# ardustatversion9.net
KiCad netlist of a schematic drawn in EAGLE
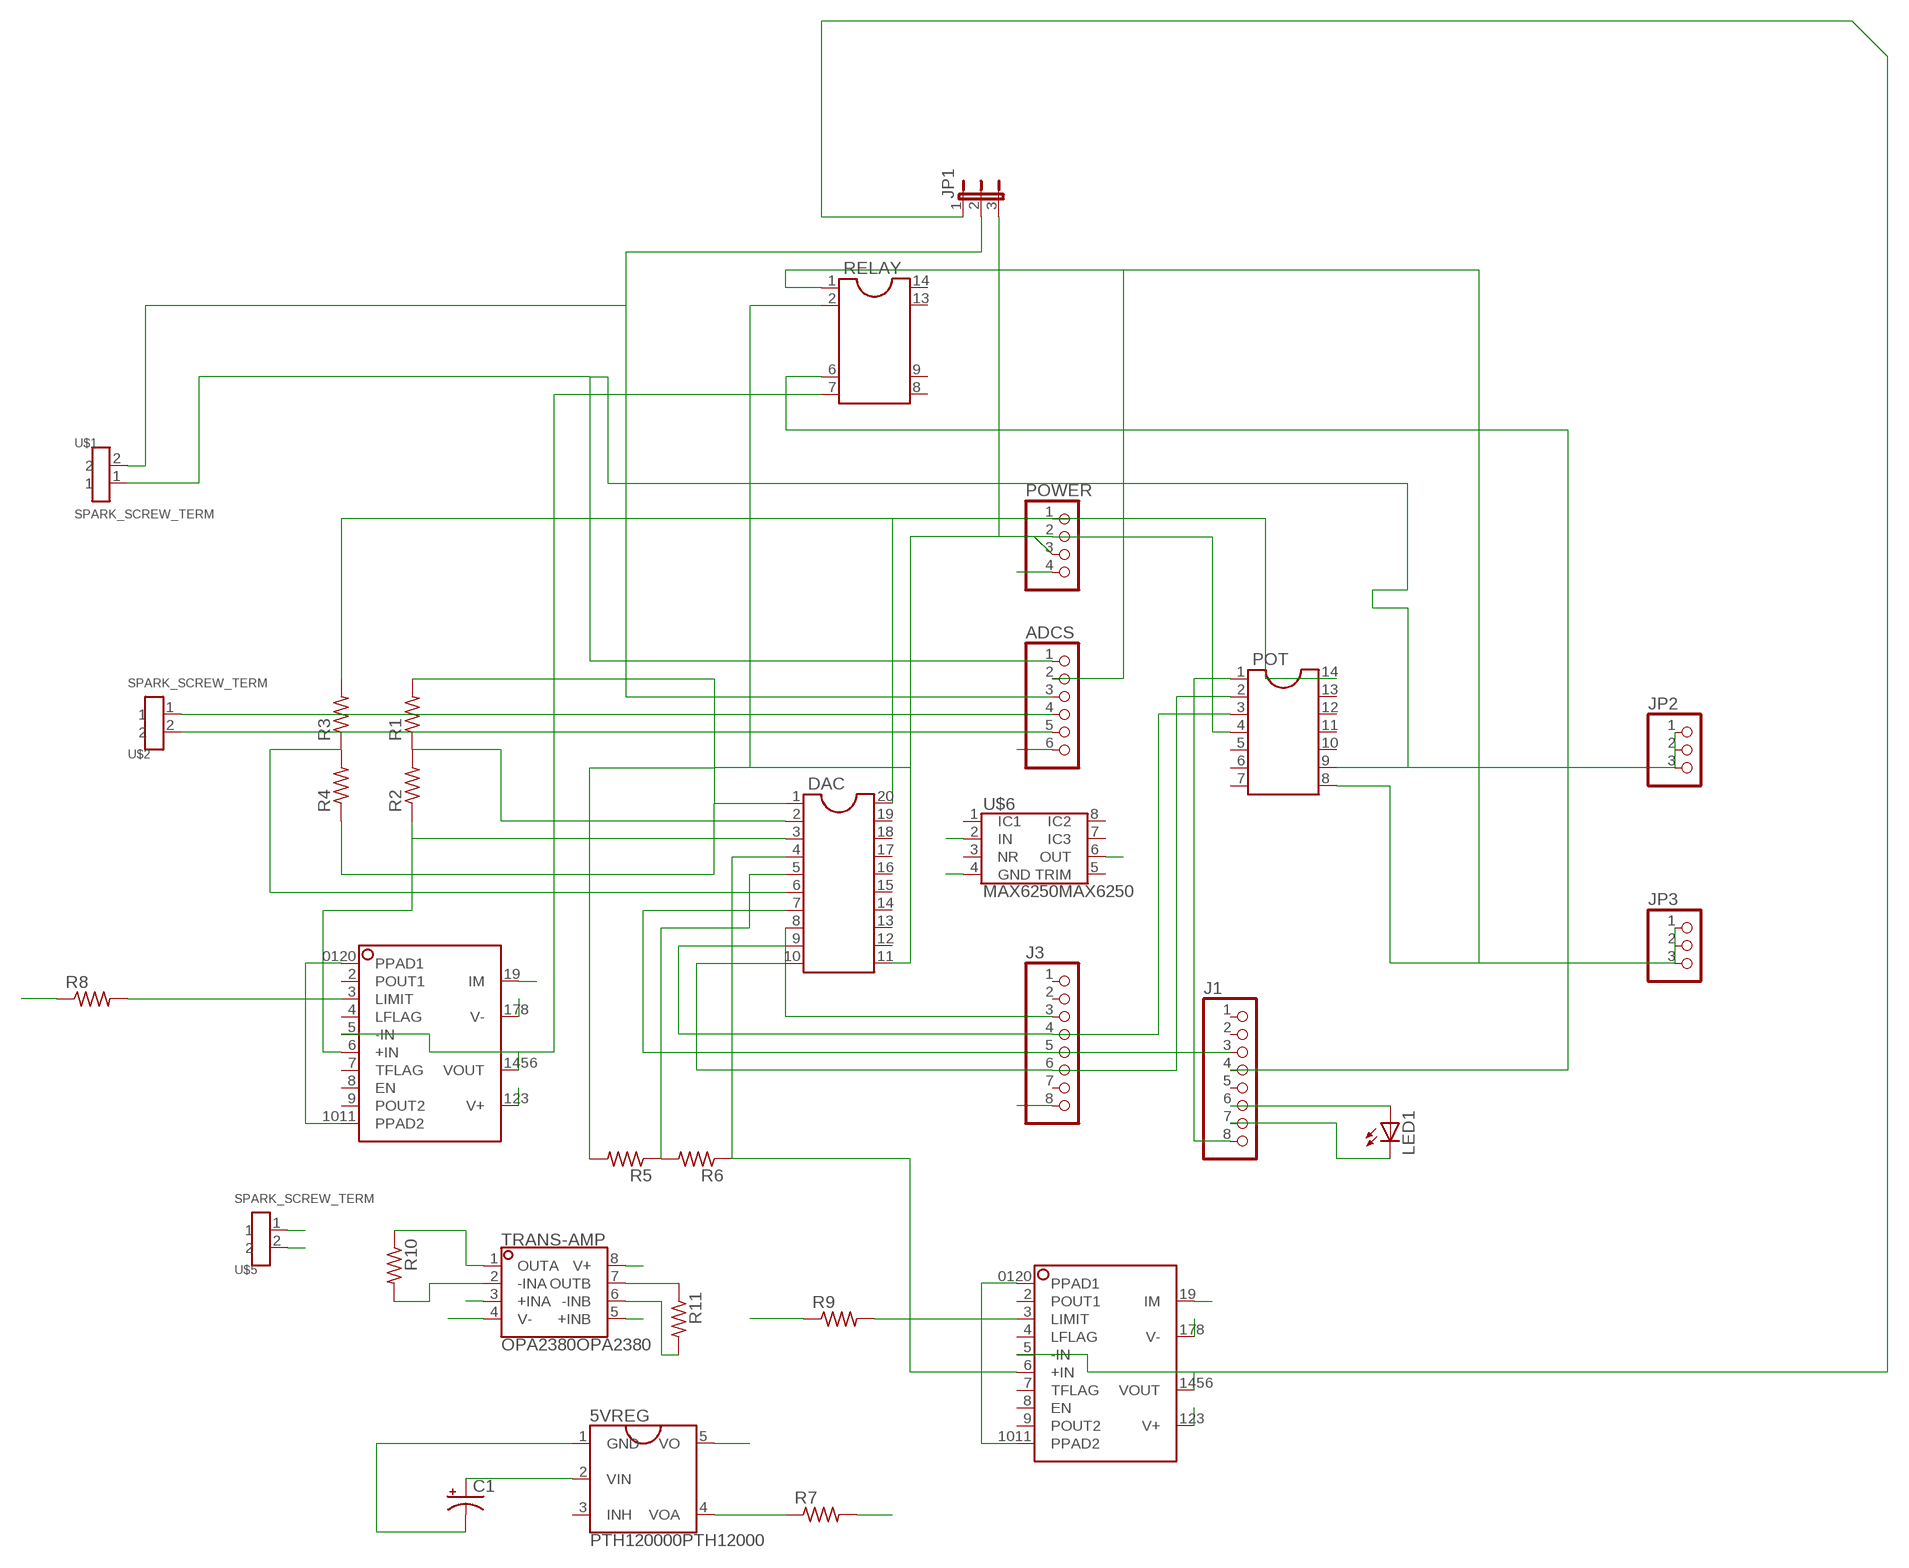
[diagram p0: schematic, sheet 1]

(export (version "E")
  (design (tool "Eeschema 10.0.6"))
  (components
    (comp (ref "5VREG")
      (value "PTH120000PTH12000")
      (footprint "eagle-import:PTH120000")
      (libsource (lib "eagle-import") (part "PTH120000PTH12000"))
    )
    (comp (ref "ADCS")
      (value "PINHD-1X6")
      (footprint "eagle-import:1X06")
      (libsource (lib "eagle-import") (part "PINHD-1X6"))
    )
    (comp (ref "C1")
      (value "CPOL-USE5-10.5")
      (footprint "eagle-import:E5-10,5")
      (libsource (lib "eagle-import") (part "CPOL-USE5-10.5"))
    )
    (comp (ref "DAC")
      (value "DIL20S")
      (footprint "eagle-import:SOCKED-20")
      (libsource (lib "eagle-import") (part "DIL20S"))
    )
    (comp (ref "J1")
      (value "PINHD-1X8")
      (footprint "eagle-import:1X08")
      (libsource (lib "eagle-import") (part "PINHD-1X8"))
    )
    (comp (ref "J3")
      (value "PINHD-1X8")
      (footprint "eagle-import:1X08")
      (libsource (lib "eagle-import") (part "PINHD-1X8"))
    )
    (comp (ref "JP1")
      (value "JP2E")
      (footprint "eagle-import:JP2")
      (libsource (lib "eagle-import") (part "JP2E"))
    )
    (comp (ref "JP2")
      (value "PINHD-1X3")
      (footprint "eagle-import:1X03")
      (libsource (lib "eagle-import") (part "PINHD-1X3"))
    )
    (comp (ref "JP3")
      (value "PINHD-1X3")
      (footprint "eagle-import:1X03")
      (libsource (lib "eagle-import") (part "PINHD-1X3"))
    )
    (comp (ref "LED1")
      (value "LED5MM")
      (footprint "eagle-import:LED5MM")
      (libsource (lib "eagle-import") (part "LED5MM"))
    )
    (comp (ref "POT")
      (value "DIL14S")
      (footprint "eagle-import:SOCKET-14")
      (libsource (lib "eagle-import") (part "DIL14S"))
    )
    (comp (ref "POWER")
      (value "PINHD-1X4")
      (footprint "eagle-import:1X04")
      (libsource (lib "eagle-import") (part "PINHD-1X4"))
    )
    (comp (ref "R1")
      (value "R-US_R1206")
      (footprint "eagle-import:R1206")
      (libsource (lib "eagle-import") (part "R-US_R1206"))
    )
    (comp (ref "R2")
      (value "R-US_R1206")
      (footprint "eagle-import:R1206")
      (libsource (lib "eagle-import") (part "resistor_R-US_R1206"))
    )
    (comp (ref "R3")
      (value "R-US_R1206")
      (footprint "eagle-import:R1206")
      (libsource (lib "eagle-import") (part "R-US_R1206"))
    )
    (comp (ref "R4")
      (value "R-US_R1206")
      (footprint "eagle-import:R1206")
      (libsource (lib "eagle-import") (part "R-US_R1206"))
    )
    (comp (ref "R5")
      (value "R-US_R1206")
      (footprint "eagle-import:R1206")
      (libsource (lib "eagle-import") (part "R-US_R1206"))
    )
    (comp (ref "R6")
      (value "R-US_R1206")
      (footprint "eagle-import:R1206")
      (libsource (lib "eagle-import") (part "R-US_R1206"))
    )
    (comp (ref "R7")
      (value "R-US_M1206")
      (footprint "eagle-import:M1206")
      (libsource (lib "eagle-import") (part "R-US_M1206"))
    )
    (comp (ref "R8")
      (value "R-US_R1206")
      (footprint "eagle-import:R1206")
      (libsource (lib "eagle-import") (part "R-US_R1206"))
    )
    (comp (ref "R9")
      (value "R-US_M1206")
      (footprint "eagle-import:M1206")
      (libsource (lib "eagle-import") (part "R-US_M1206"))
    )
    (comp (ref "R10")
      (value "R-US_M1206")
      (footprint "eagle-import:M1206")
      (libsource (lib "eagle-import") (part "R-US_M1206"))
    )
    (comp (ref "R11")
      (value "R-US_M1206")
      (footprint "eagle-import:M1206")
      (libsource (lib "eagle-import") (part "R-US_M1206"))
    )
    (comp (ref "RELAY")
      (value "DIL14/8")
      (footprint "eagle-import:DIL14_8")
      (libsource (lib "eagle-import") (part "DIL14/8"))
    )
    (comp (ref "TRANS-AMP")
      (value "OPA2380OPA2380")
      (footprint "eagle-import:OPA2380")
      (libsource (lib "eagle-import") (part "OPA2380OPA2380"))
    )
    (comp (ref "U$1")
      (value "SPARK_SCREW_TERM")
      (footprint "eagle-import:SPARK_SCREW_TERM")
      (libsource (lib "eagle-import") (part "SPARK_SCREW_TERM"))
    )
    (comp (ref "U$2")
      (value "SPARK_SCREW_TERM")
      (footprint "eagle-import:SPARK_SCREW_TERM")
      (libsource (lib "eagle-import") (part "SPARK_SCREW_TERM"))
    )
    (comp (ref "U$3")
      (value "OPA569OPA569")
      (footprint "eagle-import:OPA569")
      (libsource (lib "eagle-import") (part "OPA569OPA569"))
    )
    (comp (ref "U$4")
      (value "OPA569OPA569")
      (footprint "eagle-import:OPA569")
      (libsource (lib "eagle-import") (part "OPA569OPA569"))
    )
    (comp (ref "U$5")
      (value "SPARK_SCREW_TERM")
      (footprint "eagle-import:SPARK_SCREW_TERM")
      (libsource (lib "eagle-import") (part "SPARK_SCREW_TERM"))
    )
    (comp (ref "U$6")
      (value "MAX6250MAX6250")
      (footprint "eagle-import:MAX6250")
      (libsource (lib "eagle-import") (part "MAX6250MAX6250"))
    )
  )
  (nets
    (net (code "1") (name "/GND") (class "Default")
      (node (ref "5VREG") (pin "1") (pinfunction "GND_1") (pintype "power_in"))
      (node (ref "C1") (pin "-") (pinfunction "-_-") (pintype "passive"))
      (node (ref "DAC") (pin "1") (pinfunction "1_1") (pintype "passive"))
      (node (ref "DAC") (pin "11") (pinfunction "11_11") (pintype "passive"))
      (node (ref "JP1") (pin "3") (pinfunction "3_3") (pintype "passive"))
      (node (ref "POT") (pin "4") (pinfunction "4_4") (pintype "passive"))
      (node (ref "POWER") (pin "2") (pinfunction "2_2") (pintype "passive"))
      (node (ref "POWER") (pin "3") (pinfunction "3_3") (pintype "passive"))
      (node (ref "R1") (pin "2") (pinfunction "2_2") (pintype "passive"))
      (node (ref "R4") (pin "1") (pinfunction "1_1") (pintype "passive"))
      (node (ref "R5") (pin "2") (pinfunction "2_2") (pintype "passive"))
      (node (ref "R7") (pin "2") (pinfunction "2_2") (pintype "passive"))
      (node (ref "R8") (pin "1") (pinfunction "1_1") (pintype "passive"))
      (node (ref "R9") (pin "1") (pinfunction "1_1") (pintype "passive"))
      (node (ref "RELAY") (pin "2") (pinfunction "2_2") (pintype "passive"))
      (node (ref "TRANS-AMP") (pin "4") (pinfunction "V-_4") (pintype "power_in"))
      (node (ref "U$3") (pin "0120") (pinfunction "PPAD1_0120") (pintype "bidirectional"))
      (node (ref "U$3") (pin "1011") (pinfunction "PPAD2_1011") (pintype "bidirectional"))
      (node (ref "U$3") (pin "178") (pinfunction "V-_178") (pintype "bidirectional"))
      (node (ref "U$4") (pin "0120") (pinfunction "PPAD1_0120") (pintype "bidirectional"))
      (node (ref "U$4") (pin "1011") (pinfunction "PPAD2_1011") (pintype "bidirectional"))
      (node (ref "U$4") (pin "178") (pinfunction "V-_178") (pintype "bidirectional"))
      (node (ref "U$5") (pin "2") (pinfunction "2_2") (pintype "bidirectional"))
      (node (ref "U$6") (pin "4") (pinfunction "GND_4") (pintype "bidirectional"))
    )
    (net (code "2") (name "/N$10") (class "Default")
      (node (ref "R10") (pin "2") (pinfunction "2_2") (pintype "passive"))
      (node (ref "TRANS-AMP") (pin "2") (pinfunction "-INA_2") (pintype "input"))
      (node (ref "U$3") (pin "19") (pinfunction "IM_19") (pintype "bidirectional"))
    )
    (net (code "3") (name "/N$11") (class "Default")
      (node (ref "ADCS") (pin "2") (pinfunction "2_2") (pintype "passive"))
      (node (ref "JP3") (pin "1") (pinfunction "1_1") (pintype "passive"))
      (node (ref "JP3") (pin "2") (pinfunction "2_2") (pintype "passive"))
      (node (ref "JP3") (pin "3") (pinfunction "3_3") (pintype "passive"))
      (node (ref "POT") (pin "8") (pinfunction "8_8") (pintype "passive"))
      (node (ref "RELAY") (pin "1") (pinfunction "1_1") (pintype "passive"))
      (node (ref "TRANS-AMP") (pin "5") (pinfunction "+INB_5") (pintype "input"))
    )
    (net (code "4") (name "/N$14") (class "Default")
      (node (ref "ADCS") (pin "5") (pinfunction "5_5") (pintype "passive"))
      (node (ref "R10") (pin "1") (pinfunction "1_1") (pintype "passive"))
      (node (ref "TRANS-AMP") (pin "1") (pinfunction "OUTA_1") (pintype "output"))
      (node (ref "U$2") (pin "2") (pinfunction "2_2") (pintype "bidirectional"))
    )
    (net (code "5") (name "/N$19") (class "Default")
      (node (ref "5VREG") (pin "5") (pinfunction "VO_5") (pintype "bidirectional"))
      (node (ref "TRANS-AMP") (pin "8") (pinfunction "V+_8") (pintype "power_in"))
      (node (ref "U$3") (pin "123") (pinfunction "V+_123") (pintype "bidirectional"))
      (node (ref "U$4") (pin "123") (pinfunction "V+_123") (pintype "bidirectional"))
    )
    (net (code "6") (name "/N$21") (class "Default")
      (node (ref "ADCS") (pin "3") (pinfunction "3_3") (pintype "passive"))
      (node (ref "JP1") (pin "2") (pinfunction "2_2") (pintype "passive"))
      (node (ref "TRANS-AMP") (pin "3") (pinfunction "+INA_3") (pintype "input"))
      (node (ref "U$1") (pin "2") (pinfunction "2_2") (pintype "bidirectional"))
    )
    (net (code "7") (name "/N$22") (class "Default")
      (node (ref "5VREG") (pin "2") (pinfunction "VIN_2") (pintype "power_in"))
      (node (ref "C1") (pin "+") (pinfunction "+_+") (pintype "passive"))
      (node (ref "POWER") (pin "4") (pinfunction "4_4") (pintype "passive"))
      (node (ref "U$5") (pin "1") (pinfunction "1_1") (pintype "bidirectional"))
      (node (ref "U$6") (pin "2") (pinfunction "IN_2") (pintype "bidirectional"))
    )
    (net (code "8") (name "/N$24") (class "Default")
      (node (ref "J3") (pin "8") (pinfunction "8_8") (pintype "passive"))
      (node (ref "U$6") (pin "6") (pinfunction "OUT_6") (pintype "bidirectional"))
    )
    (net (code "9") (name "/N$48") (class "Default")
      (node (ref "ADCS") (pin "6") (pinfunction "6_6") (pintype "passive"))
      (node (ref "R11") (pin "1") (pinfunction "1_1") (pintype "passive"))
      (node (ref "TRANS-AMP") (pin "7") (pinfunction "OUTB_7") (pintype "output"))
    )
    (net (code "10") (name "/N$49") (class "Default")
      (node (ref "R11") (pin "2") (pinfunction "2_2") (pintype "passive"))
      (node (ref "TRANS-AMP") (pin "6") (pinfunction "-INB_6") (pintype "input"))
      (node (ref "U$4") (pin "19") (pinfunction "IM_19") (pintype "bidirectional"))
    )
    (net (code "11") (name "Net-(5VREG-VOA)") (class "Default")
      (node (ref "5VREG") (pin "4") (pinfunction "VOA_4") (pintype "input"))
      (node (ref "R7") (pin "1") (pinfunction "1_1") (pintype "passive"))
    )
    (net (code "12") (name "Net-(ADCS-Pad1)") (class "Default")
      (node (ref "ADCS") (pin "1") (pinfunction "1_1") (pintype "passive"))
      (node (ref "JP2") (pin "1") (pinfunction "1_1") (pintype "passive"))
      (node (ref "JP2") (pin "2") (pinfunction "2_2") (pintype "passive"))
      (node (ref "JP2") (pin "3") (pinfunction "3_3") (pintype "passive"))
      (node (ref "POT") (pin "9") (pinfunction "9_9") (pintype "passive"))
      (node (ref "U$1") (pin "1") (pinfunction "1_1") (pintype "bidirectional"))
    )
    (net (code "13") (name "Net-(ADCS-Pad4)") (class "Default")
      (node (ref "ADCS") (pin "4") (pinfunction "4_4") (pintype "passive"))
      (node (ref "U$2") (pin "1") (pinfunction "1_1") (pintype "bidirectional"))
    )
    (net (code "14") (name "Net-(DAC-Pad2)") (class "Default")
      (node (ref "DAC") (pin "2") (pinfunction "2_2") (pintype "passive"))
      (node (ref "R1") (pin "1") (pinfunction "1_1") (pintype "passive"))
      (node (ref "R2") (pin "2") (pinfunction "2_2") (pintype "passive"))
    )
    (net (code "15") (name "Net-(DAC-Pad5)") (class "Default")
      (node (ref "DAC") (pin "5") (pinfunction "5_5") (pintype "passive"))
      (node (ref "R5") (pin "1") (pinfunction "1_1") (pintype "passive"))
      (node (ref "R6") (pin "2") (pinfunction "2_2") (pintype "passive"))
    )
    (net (code "16") (name "Net-(DAC-Pad6)") (class "Default")
      (node (ref "DAC") (pin "6") (pinfunction "6_6") (pintype "passive"))
      (node (ref "R3") (pin "1") (pinfunction "1_1") (pintype "passive"))
      (node (ref "R4") (pin "2") (pinfunction "2_2") (pintype "passive"))
    )
    (net (code "17") (name "Net-(DAC-Pad7)") (class "Default")
      (node (ref "DAC") (pin "7") (pinfunction "7_7") (pintype "passive"))
      (node (ref "J1") (pin "3") (pinfunction "3_3") (pintype "passive"))
    )
    (net (code "18") (name "Net-(DAC-Pad8)") (class "Default")
      (node (ref "DAC") (pin "8") (pinfunction "8_8") (pintype "passive"))
      (node (ref "J3") (pin "3") (pinfunction "3_3") (pintype "passive"))
    )
    (net (code "19") (name "Net-(DAC-Pad9)") (class "Default")
      (node (ref "DAC") (pin "9") (pinfunction "9_9") (pintype "passive"))
      (node (ref "J3") (pin "4") (pinfunction "4_4") (pintype "passive"))
      (node (ref "POT") (pin "3") (pinfunction "3_3") (pintype "passive"))
    )
    (net (code "20") (name "Net-(DAC-Pad10)") (class "Default")
      (node (ref "DAC") (pin "10") (pinfunction "10_10") (pintype "passive"))
      (node (ref "J3") (pin "6") (pinfunction "6_6") (pintype "passive"))
      (node (ref "POT") (pin "2") (pinfunction "2_2") (pintype "passive"))
    )
    (net (code "21") (name "Net-(DAC-Pad20)") (class "Default")
      (node (ref "DAC") (pin "20") (pinfunction "20_20") (pintype "passive"))
      (node (ref "POT") (pin "14") (pinfunction "14_14") (pintype "passive"))
      (node (ref "POWER") (pin "1") (pinfunction "1_1") (pintype "passive"))
      (node (ref "R3") (pin "2") (pinfunction "2_2") (pintype "passive"))
    )
    (net (code "22") (name "Net-(J1-Pad4)") (class "Default")
      (node (ref "J1") (pin "4") (pinfunction "4_4") (pintype "passive"))
      (node (ref "RELAY") (pin "6") (pinfunction "6_6") (pintype "passive"))
    )
    (net (code "23") (name "Net-(J1-Pad6)") (class "Default")
      (node (ref "J1") (pin "6") (pinfunction "6_6") (pintype "passive"))
      (node (ref "LED1") (pin "A") (pinfunction "A_A") (pintype "passive"))
    )
    (net (code "24") (name "Net-(J1-Pad8)") (class "Default")
      (node (ref "J1") (pin "8") (pinfunction "8_8") (pintype "passive"))
      (node (ref "POT") (pin "1") (pinfunction "1_1") (pintype "passive"))
    )
    (net (code "25") (name "Net-(LED1-C)") (class "Default")
      (node (ref "J1") (pin "7") (pinfunction "7_7") (pintype "passive"))
      (node (ref "LED1") (pin "K") (pinfunction "C_K") (pintype "passive"))
    )
    (net (code "26") (name "Net-(U$3-+IN)") (class "Default")
      (node (ref "DAC") (pin "3") (pinfunction "3_3") (pintype "passive"))
      (node (ref "R2") (pin "1") (pinfunction "1_1") (pintype "passive"))
      (node (ref "U$3") (pin "6") (pinfunction "+IN_6") (pintype "bidirectional"))
    )
    (net (code "27") (name "Net-(U$3--IN)") (class "Default")
      (node (ref "RELAY") (pin "7") (pinfunction "7_7") (pintype "passive"))
      (node (ref "U$3") (pin "1456") (pinfunction "VOUT_1456") (pintype "bidirectional"))
      (node (ref "U$3") (pin "5") (pinfunction "-IN_5") (pintype "bidirectional"))
    )
    (net (code "28") (name "Net-(U$3-LIMIT)") (class "Default")
      (node (ref "R8") (pin "2") (pinfunction "2_2") (pintype "passive"))
      (node (ref "U$3") (pin "3") (pinfunction "LIMIT_3") (pintype "bidirectional"))
    )
    (net (code "29") (name "Net-(U$4-+IN)") (class "Default")
      (node (ref "DAC") (pin "4") (pinfunction "4_4") (pintype "passive"))
      (node (ref "R6") (pin "1") (pinfunction "1_1") (pintype "passive"))
      (node (ref "U$4") (pin "6") (pinfunction "+IN_6") (pintype "bidirectional"))
    )
    (net (code "30") (name "Net-(U$4--IN)") (class "Default")
      (node (ref "JP1") (pin "1") (pinfunction "1_1") (pintype "passive"))
      (node (ref "U$4") (pin "1456") (pinfunction "VOUT_1456") (pintype "bidirectional"))
      (node (ref "U$4") (pin "5") (pinfunction "-IN_5") (pintype "bidirectional"))
    )
    (net (code "31") (name "Net-(U$4-LIMIT)") (class "Default")
      (node (ref "R9") (pin "2") (pinfunction "2_2") (pintype "passive"))
      (node (ref "U$4") (pin "3") (pinfunction "LIMIT_3") (pintype "bidirectional"))
    )
    (net (code "32") (name "unconnected-(5VREG-INH-Pad3)") (class "Default")
      (node (ref "5VREG") (pin "3") (pinfunction "INH_3") (pintype "input"))
    )
    (net (code "33") (name "unconnected-(DAC-Pad12)") (class "Default")
      (node (ref "DAC") (pin "12") (pinfunction "12_12") (pintype "passive"))
    )
    (net (code "34") (name "unconnected-(DAC-Pad13)") (class "Default")
      (node (ref "DAC") (pin "13") (pinfunction "13_13") (pintype "passive"))
    )
    (net (code "35") (name "unconnected-(DAC-Pad14)") (class "Default")
      (node (ref "DAC") (pin "14") (pinfunction "14_14") (pintype "passive"))
    )
    (net (code "36") (name "unconnected-(DAC-Pad15)") (class "Default")
      (node (ref "DAC") (pin "15") (pinfunction "15_15") (pintype "passive"))
    )
    (net (code "37") (name "unconnected-(DAC-Pad16)") (class "Default")
      (node (ref "DAC") (pin "16") (pinfunction "16_16") (pintype "passive"))
    )
    (net (code "38") (name "unconnected-(DAC-Pad17)") (class "Default")
      (node (ref "DAC") (pin "17") (pinfunction "17_17") (pintype "passive"))
    )
    (net (code "39") (name "unconnected-(DAC-Pad18)") (class "Default")
      (node (ref "DAC") (pin "18") (pinfunction "18_18") (pintype "passive"))
    )
    (net (code "40") (name "unconnected-(DAC-Pad19)") (class "Default")
      (node (ref "DAC") (pin "19") (pinfunction "19_19") (pintype "passive"))
    )
    (net (code "41") (name "unconnected-(J1-Pad1)") (class "Default")
      (node (ref "J1") (pin "1") (pinfunction "1_1") (pintype "passive"))
    )
    (net (code "42") (name "unconnected-(J1-Pad2)") (class "Default")
      (node (ref "J1") (pin "2") (pinfunction "2_2") (pintype "passive"))
    )
    (net (code "43") (name "unconnected-(J1-Pad5)") (class "Default")
      (node (ref "J1") (pin "5") (pinfunction "5_5") (pintype "passive"))
    )
    (net (code "44") (name "unconnected-(J3-Pad1)") (class "Default")
      (node (ref "J3") (pin "1") (pinfunction "1_1") (pintype "passive"))
    )
    (net (code "45") (name "unconnected-(J3-Pad2)") (class "Default")
      (node (ref "J3") (pin "2") (pinfunction "2_2") (pintype "passive"))
    )
    (net (code "46") (name "unconnected-(J3-Pad5)") (class "Default")
      (node (ref "J3") (pin "5") (pinfunction "5_5") (pintype "passive"))
    )
    (net (code "47") (name "unconnected-(J3-Pad7)") (class "Default")
      (node (ref "J3") (pin "7") (pinfunction "7_7") (pintype "passive"))
    )
    (net (code "48") (name "unconnected-(POT-Pad5)") (class "Default")
      (node (ref "POT") (pin "5") (pinfunction "5_5") (pintype "passive"))
    )
    (net (code "49") (name "unconnected-(POT-Pad6)") (class "Default")
      (node (ref "POT") (pin "6") (pinfunction "6_6") (pintype "passive"))
    )
    (net (code "50") (name "unconnected-(POT-Pad7)") (class "Default")
      (node (ref "POT") (pin "7") (pinfunction "7_7") (pintype "passive"))
    )
    (net (code "51") (name "unconnected-(POT-Pad10)") (class "Default")
      (node (ref "POT") (pin "10") (pinfunction "10_10") (pintype "passive"))
    )
    (net (code "52") (name "unconnected-(POT-Pad11)") (class "Default")
      (node (ref "POT") (pin "11") (pinfunction "11_11") (pintype "passive"))
    )
    (net (code "53") (name "unconnected-(POT-Pad12)") (class "Default")
      (node (ref "POT") (pin "12") (pinfunction "12_12") (pintype "passive"))
    )
    (net (code "54") (name "unconnected-(POT-Pad13)") (class "Default")
      (node (ref "POT") (pin "13") (pinfunction "13_13") (pintype "passive"))
    )
    (net (code "55") (name "unconnected-(RELAY-Pad8)") (class "Default")
      (node (ref "RELAY") (pin "8") (pinfunction "8_8") (pintype "passive"))
    )
    (net (code "56") (name "unconnected-(RELAY-Pad9)") (class "Default")
      (node (ref "RELAY") (pin "9") (pinfunction "9_9") (pintype "passive"))
    )
    (net (code "57") (name "unconnected-(RELAY-Pad13)") (class "Default")
      (node (ref "RELAY") (pin "13") (pinfunction "13_13") (pintype "passive"))
    )
    (net (code "58") (name "unconnected-(RELAY-Pad14)") (class "Default")
      (node (ref "RELAY") (pin "14") (pinfunction "14_14") (pintype "passive"))
    )
    (net (code "59") (name "unconnected-(U$3-EN-Pad8)") (class "Default")
      (node (ref "U$3") (pin "8") (pinfunction "EN_8") (pintype "bidirectional"))
    )
    (net (code "60") (name "unconnected-(U$3-LFLAG-Pad4)") (class "Default")
      (node (ref "U$3") (pin "4") (pinfunction "LFLAG_4") (pintype "bidirectional"))
    )
    (net (code "61") (name "unconnected-(U$3-POUT1-Pad2)") (class "Default")
      (node (ref "U$3") (pin "2") (pinfunction "POUT1_2") (pintype "bidirectional"))
    )
    (net (code "62") (name "unconnected-(U$3-POUT2-Pad9)") (class "Default")
      (node (ref "U$3") (pin "9") (pinfunction "POUT2_9") (pintype "bidirectional"))
    )
    (net (code "63") (name "unconnected-(U$3-TFLAG-Pad7)") (class "Default")
      (node (ref "U$3") (pin "7") (pinfunction "TFLAG_7") (pintype "bidirectional"))
    )
    (net (code "64") (name "unconnected-(U$4-EN-Pad8)") (class "Default")
      (node (ref "U$4") (pin "8") (pinfunction "EN_8") (pintype "bidirectional"))
    )
    (net (code "65") (name "unconnected-(U$4-LFLAG-Pad4)") (class "Default")
      (node (ref "U$4") (pin "4") (pinfunction "LFLAG_4") (pintype "bidirectional"))
    )
    (net (code "66") (name "unconnected-(U$4-POUT1-Pad2)") (class "Default")
      (node (ref "U$4") (pin "2") (pinfunction "POUT1_2") (pintype "bidirectional"))
    )
    (net (code "67") (name "unconnected-(U$4-POUT2-Pad9)") (class "Default")
      (node (ref "U$4") (pin "9") (pinfunction "POUT2_9") (pintype "bidirectional"))
    )
    (net (code "68") (name "unconnected-(U$4-TFLAG-Pad7)") (class "Default")
      (node (ref "U$4") (pin "7") (pinfunction "TFLAG_7") (pintype "bidirectional"))
    )
    (net (code "69") (name "unconnected-(U$6-IC1-Pad1)") (class "Default")
      (node (ref "U$6") (pin "1") (pinfunction "IC1_1") (pintype "bidirectional"))
    )
    (net (code "70") (name "unconnected-(U$6-IC2-Pad8)") (class "Default")
      (node (ref "U$6") (pin "8") (pinfunction "IC2_8") (pintype "bidirectional"))
    )
    (net (code "71") (name "unconnected-(U$6-IC3-Pad7)") (class "Default")
      (node (ref "U$6") (pin "7") (pinfunction "IC3_7") (pintype "bidirectional"))
    )
    (net (code "72") (name "unconnected-(U$6-NR-Pad3)") (class "Default")
      (node (ref "U$6") (pin "3") (pinfunction "NR_3") (pintype "bidirectional"))
    )
    (net (code "73") (name "unconnected-(U$6-TRIM-Pad5)") (class "Default")
      (node (ref "U$6") (pin "5") (pinfunction "TRIM_5") (pintype "bidirectional"))
    )
  )
)
